# self.net
KiCad netlist of a schematic drawn in Altium Designer
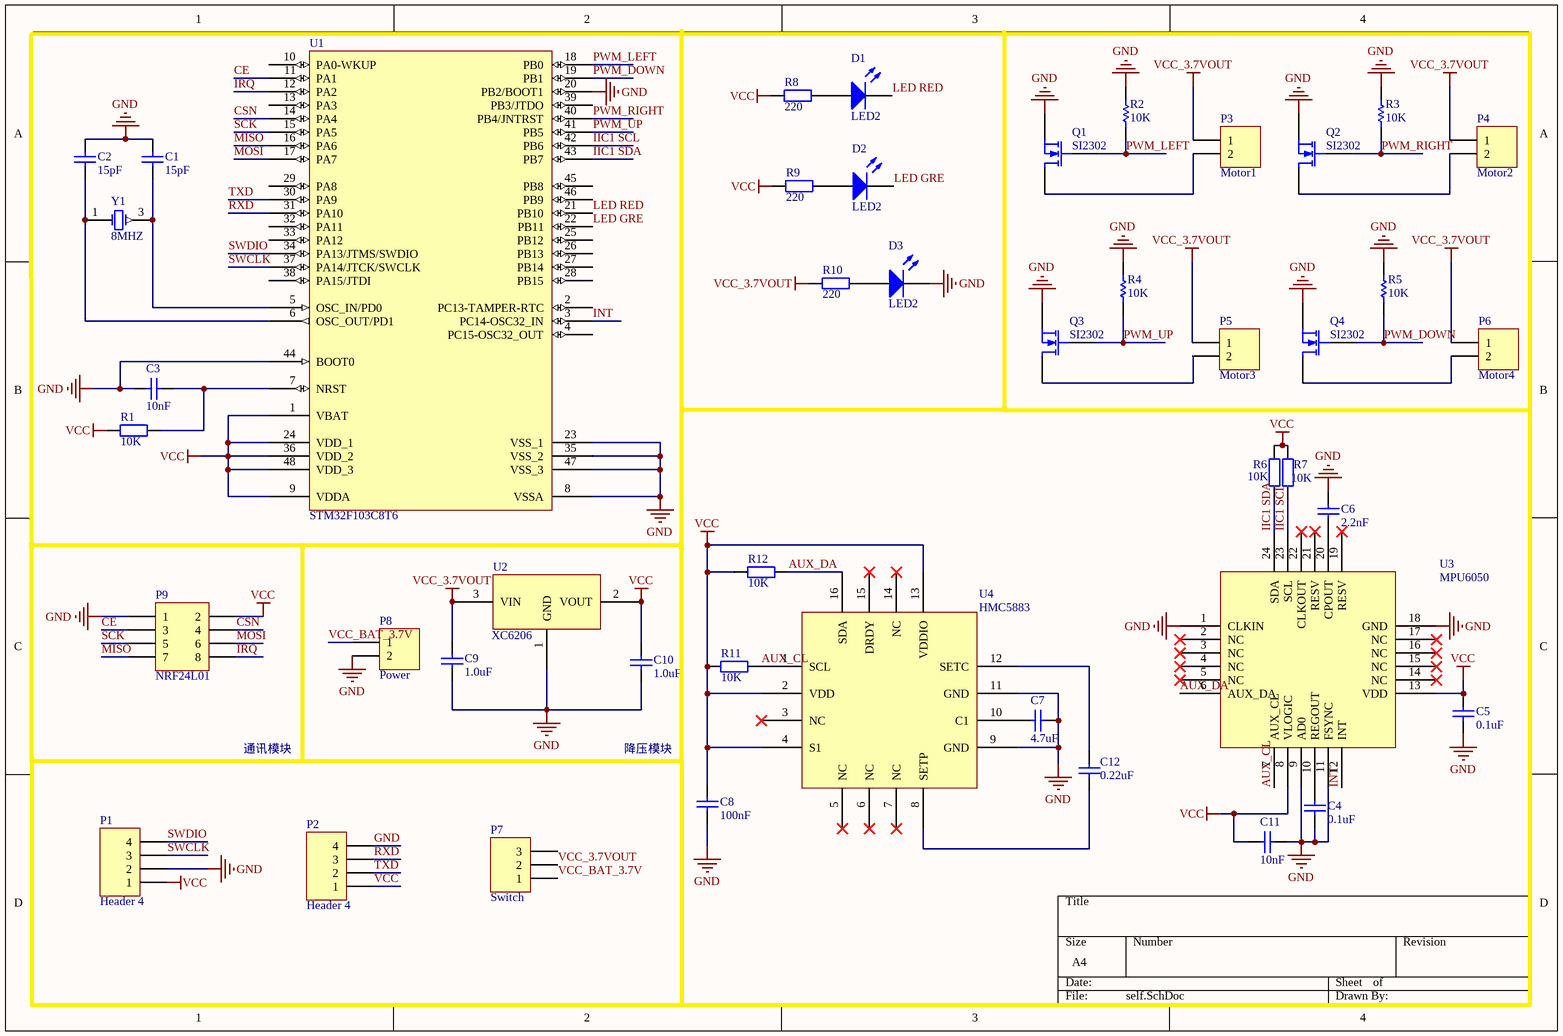
[diagram p0: self.SchDoc]

(export (version "E")
  (design (tool "Eeschema 10.0.6"))
  (components
    (comp (ref "C1")
      (value "15pF")
      (footprint "0603-N-CAP")
      (description "Capacitor (Semiconductor SIM Model)")
      (fields (field (name "Comment") "Cap Semi") (field (name "PUBLISHER") "Altium Limited"))
      (libsource (lib "Miscellaneous Devices") (part "Cap Semi"))
    )
    (comp (ref "C2")
      (value "15pF")
      (footprint "0603-N-CAP")
      (description "Capacitor (Semiconductor SIM Model)")
      (fields (field (name "Comment") "Cap Semi") (field (name "PUBLISHER") "Altium Limited"))
      (libsource (lib "Miscellaneous Devices") (part "Cap Semi"))
    )
    (comp (ref "C3")
      (value "10nF")
      (footprint "0603-N-CAP")
      (description "Capacitor (Semiconductor SIM Model)")
      (fields (field (name "Comment") "Cap Semi") (field (name "PUBLISHER") "Altium Limited"))
      (libsource (lib "Miscellaneous Devices") (part "Cap Semi"))
    )
    (comp (ref "C4")
      (value "0.1uF")
      (footprint "0603-N-CAP")
      (description "Capacitor (Semiconductor SIM Model)")
      (fields (field (name "Comment") "Cap Semi") (field (name "PUBLISHER") "Altium Limited"))
      (libsource (lib "Miscellaneous Devices") (part "Cap Semi"))
    )
    (comp (ref "C5")
      (value "0.1uF")
      (footprint "0603-N-CAP")
      (description "Capacitor (Semiconductor SIM Model)")
      (fields (field (name "Comment") "Cap Semi") (field (name "PUBLISHER") "Altium Limited"))
      (libsource (lib "Miscellaneous Devices") (part "Cap Semi"))
    )
    (comp (ref "C6")
      (value "2.2nF")
      (footprint "0603-N-CAP")
      (description "Capacitor (Semiconductor SIM Model)")
      (fields (field (name "Comment") "Cap Semi") (field (name "PUBLISHER") "Altium Limited"))
      (libsource (lib "Miscellaneous Devices") (part "Cap Semi"))
    )
    (comp (ref "C7")
      (value "4.7uF")
      (footprint "0603-N-CAP")
      (description "Capacitor (Semiconductor SIM Model)")
      (fields (field (name "Comment") "Cap Semi") (field (name "PUBLISHER") "Altium Limited"))
      (libsource (lib "Miscellaneous Devices") (part "Cap Semi"))
    )
    (comp (ref "C8")
      (value "100nF")
      (footprint "0603-N-CAP")
      (description "Capacitor (Semiconductor SIM Model)")
      (fields (field (name "Comment") "Cap Semi") (field (name "PUBLISHER") "Altium Limited"))
      (libsource (lib "Miscellaneous Devices") (part "Cap Semi"))
    )
    (comp (ref "C9")
      (value "1.0uF")
      (footprint "0603-N-CAP")
      (description "Capacitor (Semiconductor SIM Model)")
      (fields (field (name "Comment") "Cap Semi") (field (name "PUBLISHER") "Altium Limited"))
      (libsource (lib "Miscellaneous Devices") (part "Cap Semi"))
    )
    (comp (ref "C10")
      (value "1.0uF")
      (footprint "0603-N-CAP")
      (description "Capacitor (Semiconductor SIM Model)")
      (fields (field (name "Comment") "Cap Semi") (field (name "PUBLISHER") "Altium Limited"))
      (libsource (lib "Miscellaneous Devices") (part "Cap Semi"))
    )
    (comp (ref "C11")
      (value "10nF")
      (footprint "0603-N-CAP")
      (description "Capacitor (Semiconductor SIM Model)")
      (fields (field (name "Comment") "Cap Semi") (field (name "PUBLISHER") "Altium Limited"))
      (libsource (lib "Miscellaneous Devices") (part "Cap Semi"))
    )
    (comp (ref "C12")
      (value "0.22uF")
      (footprint "0603-N-CAP")
      (description "Capacitor (Semiconductor SIM Model)")
      (fields (field (name "Comment") "Cap Semi") (field (name "PUBLISHER") "Altium Limited"))
      (libsource (lib "Miscellaneous Devices") (part "Cap Semi"))
    )
    (comp (ref "D1")
      (value "LED2")
      (footprint "6-0805_N")
      (description "Typical RED, GREEN, YELLOW, AMBER GaAs LED")
      (fields (field (name "PUBLISHER") "Altium Limited"))
      (libsource (lib "Miscellaneous Devices") (part "LED2"))
    )
    (comp (ref "D2")
      (value "LED2")
      (footprint "6-0805_N")
      (description "Typical RED, GREEN, YELLOW, AMBER GaAs LED")
      (fields (field (name "PUBLISHER") "Altium Limited"))
      (libsource (lib "Miscellaneous Devices") (part "LED2"))
    )
    (comp (ref "D3")
      (value "LED2")
      (footprint "6-0805_N")
      (description "Typical RED, GREEN, YELLOW, AMBER GaAs LED")
      (fields (field (name "PUBLISHER") "Altium Limited"))
      (libsource (lib "Miscellaneous Devices") (part "LED2"))
    )
    (comp (ref "P1")
      (value "Header 4")
      (footprint "SW_download")
      (description "Header, 4-Pin")
      (fields (field (name "PUBLISHER") "Altium Limited"))
      (libsource (lib "Miscellaneous Connectors") (part "Header 4"))
    )
    (comp (ref "P2")
      (value "Header 4")
      (footprint "HDR1X4")
      (description "Header, 4-Pin")
      (fields (field (name "PUBLISHER") "Altium Limited"))
      (libsource (lib "Miscellaneous Connectors") (part "Header 4"))
    )
    (comp (ref "P3")
      (value "Motor1")
      (footprint "Motor")
      (description "Header, 2-Pin")
      (fields (field (name "PUBLISHER") "Altium Limited"))
      (libsource (lib "Miscellaneous Connectors") (part "Header 2"))
    )
    (comp (ref "P4")
      (value "Motor2")
      (footprint "Motor")
      (description "Header, 2-Pin")
      (fields (field (name "PUBLISHER") "Altium Limited"))
      (libsource (lib "Miscellaneous Connectors") (part "Header 2"))
    )
    (comp (ref "P5")
      (value "Motor3")
      (footprint "Motor")
      (description "Header, 2-Pin")
      (fields (field (name "PUBLISHER") "Altium Limited"))
      (libsource (lib "Miscellaneous Connectors") (part "Header 2"))
    )
    (comp (ref "P6")
      (value "Motor4")
      (footprint "Motor")
      (description "Header, 2-Pin")
      (fields (field (name "PUBLISHER") "Altium Limited"))
      (libsource (lib "Miscellaneous Connectors") (part "Header 2"))
    )
    (comp (ref "P7")
      (value "Switch")
      (footprint "SWITCH")
      (description "Header, 3-Pin")
      (fields (field (name "PUBLISHER") "Altium Limited"))
      (libsource (lib "Miscellaneous Connectors") (part "Header 3"))
    )
    (comp (ref "P8")
      (value "Power")
      (footprint "0805")
      (description "Header, 2-Pin")
      (fields (field (name "PUBLISHER") "Altium Limited"))
      (libsource (lib "Miscellaneous Connectors") (part "Header 2"))
    )
    (comp (ref "P9")
      (value "NRF24L01")
      (footprint "HDR2X4")
      (description "Header, 4-Pin, Dual row, Right Angle")
      (fields (field (name "PUBLISHER") "Altium Limited"))
      (libsource (lib "Miscellaneous Connectors") (part "Header 4X2H"))
    )
    (comp (ref "Q1")
      (value "SI2302")
      (footprint "SOT-23")
      (description "N-Channel MOSFET")
      (fields (field (name "PUBLISHER") "Altium Limited"))
      (libsource (lib "Miscellaneous Devices") (part "MOSFET-N"))
    )
    (comp (ref "Q2")
      (value "SI2302")
      (footprint "SOT-23")
      (description "N-Channel MOSFET")
      (fields (field (name "PUBLISHER") "Altium Limited"))
      (libsource (lib "Miscellaneous Devices") (part "MOSFET-N"))
    )
    (comp (ref "Q3")
      (value "SI2302")
      (footprint "SOT-23")
      (description "N-Channel MOSFET")
      (fields (field (name "PUBLISHER") "Altium Limited"))
      (libsource (lib "Miscellaneous Devices") (part "MOSFET-N"))
    )
    (comp (ref "Q4")
      (value "SI2302")
      (footprint "SOT-23")
      (description "N-Channel MOSFET")
      (fields (field (name "PUBLISHER") "Altium Limited"))
      (libsource (lib "Miscellaneous Devices") (part "MOSFET-N"))
    )
    (comp (ref "R1")
      (value "10K")
      (footprint "0603-N-res")
      (description "Resistor")
      (fields (field (name "Comment") "Res2") (field (name "PUBLISHER") "Altium Limited"))
      (libsource (lib "") (part "Res2_1"))
    )
    (comp (ref "R2")
      (value "10K")
      (footprint "0603-N-res")
      (description "Resistor")
      (fields (field (name "Comment") "Res1") (field (name "PUBLISHER") "Altium Limited"))
      (libsource (lib "Miscellaneous Devices") (part "Res1"))
    )
    (comp (ref "R3")
      (value "10K")
      (footprint "0603-N-res")
      (description "Resistor")
      (fields (field (name "Comment") "Res1") (field (name "PUBLISHER") "Altium Limited"))
      (libsource (lib "Miscellaneous Devices") (part "Res1"))
    )
    (comp (ref "R4")
      (value "10K")
      (footprint "0603-N-res")
      (description "Resistor")
      (fields (field (name "Comment") "Res1") (field (name "PUBLISHER") "Altium Limited"))
      (libsource (lib "Miscellaneous Devices") (part "Res1"))
    )
    (comp (ref "R5")
      (value "10K")
      (footprint "0603-N-res")
      (description "Resistor")
      (fields (field (name "Comment") "Res1") (field (name "PUBLISHER") "Altium Limited"))
      (libsource (lib "Miscellaneous Devices") (part "Res1"))
    )
    (comp (ref "R6")
      (value "10K")
      (footprint "0603-N-res")
      (description "Resistor")
      (fields (field (name "Comment") "Res2") (field (name "PUBLISHER") "Altium Limited"))
      (libsource (lib "Miscellaneous Devices") (part "Res2"))
    )
    (comp (ref "R7")
      (value "10K")
      (footprint "0603-N-res")
      (description "Resistor")
      (fields (field (name "Comment") "Res2") (field (name "PUBLISHER") "Altium Limited"))
      (libsource (lib "Miscellaneous Devices") (part "Res2"))
    )
    (comp (ref "R8")
      (value "220")
      (footprint "0603-N-res")
      (description "Resistor")
      (fields (field (name "Comment") "Res2") (field (name "PUBLISHER") "Altium Limited"))
      (libsource (lib "") (part "Res2_1"))
    )
    (comp (ref "R9")
      (value "220")
      (footprint "0603-N-res")
      (description "Resistor")
      (fields (field (name "Comment") "Res2") (field (name "PUBLISHER") "Altium Limited"))
      (libsource (lib "") (part "Res2_1"))
    )
    (comp (ref "R10")
      (value "220")
      (footprint "0603-N-res")
      (description "Resistor")
      (fields (field (name "Comment") "Res2") (field (name "PUBLISHER") "Altium Limited"))
      (libsource (lib "") (part "Res2_1"))
    )
    (comp (ref "R11")
      (value "10K")
      (footprint "0603-N-res")
      (description "Resistor")
      (fields (field (name "Comment") "Res2") (field (name "PUBLISHER") "Altium Limited"))
      (libsource (lib "") (part "Res2_1"))
    )
    (comp (ref "R12")
      (value "10K")
      (footprint "0603-N-res")
      (description "Resistor")
      (fields (field (name "Comment") "Res2") (field (name "PUBLISHER") "Altium Limited"))
      (libsource (lib "") (part "Res2_1"))
    )
    (comp (ref "U1")
      (value "STM32F103C8T6")
      (footprint "LQFP48_N")
      (description "STM32 ARM-based 32-bit MCU with 64 Kbytes Flash, 48-pin LQFP, Industrial Temperature")
      (fields (field (name "PUBLISHER") "Altium Limited"))
      (libsource (lib "ST Microcontroller 32-Bit STM32") (part "STM32F103C8T6"))
    )
    (comp (ref "U2") (value "XC6206") (footprint "SOT-23") (libsource (lib "Mine") (part "XC6206")))
    (comp (ref "U3") (value "MPU6050") (libsource (lib "Mine") (part "MPU6050")))
    (comp (ref "U4") (value "HMC5883") (footprint "HMC5883L") (libsource (lib "Mine") (part "HMC5883")))
    (comp (ref "Y1")
      (value "8MHZ")
      (footprint "5032")
      (description "Crystal Oscillator")
      (fields (field (name "PUBLISHER") "Altium Limited"))
      (libsource (lib "Miscellaneous Devices") (part "XTAL"))
    )
  )
  (nets
    (net (code "1") (name "/AUX_CL") (class "Default")
      (node (ref "R11") (pin "1") (pinfunction "1_1") (pintype "passive"))
      (node (ref "U3") (pin "7") (pinfunction "AUX_CL_7") (pintype "passive"))
      (node (ref "U4") (pin "1") (pinfunction "SCL_1") (pintype "passive"))
    )
    (net (code "2") (name "/AUX_DA") (class "Default")
      (node (ref "R12") (pin "1") (pinfunction "1_1") (pintype "passive"))
      (node (ref "U3") (pin "6") (pinfunction "AUX_DA_6") (pintype "passive"))
      (node (ref "U4") (pin "16") (pinfunction "SDA_16") (pintype "passive"))
    )
    (net (code "3") (name "/CE") (class "Default")
      (node (ref "P9") (pin "3") (pinfunction "3_3") (pintype "passive"))
      (node (ref "U1") (pin "11") (pinfunction "PA1_11") (pintype "bidirectional"))
    )
    (net (code "4") (name "/CSN") (class "Default")
      (node (ref "P9") (pin "4") (pinfunction "4_4") (pintype "passive"))
      (node (ref "U1") (pin "14") (pinfunction "PA4_14") (pintype "bidirectional"))
    )
    (net (code "5") (name "/IIC1 SCL") (class "Default")
      (node (ref "R7") (pin "1") (pinfunction "1_1") (pintype "passive"))
      (node (ref "U1") (pin "42") (pinfunction "PB6_42") (pintype "bidirectional"))
      (node (ref "U3") (pin "23") (pinfunction "SCL_23") (pintype "passive"))
    )
    (net (code "6") (name "/IIC1 SDA") (class "Default")
      (node (ref "R6") (pin "1") (pinfunction "1_1") (pintype "passive"))
      (node (ref "U1") (pin "43") (pinfunction "PB7_43") (pintype "bidirectional"))
      (node (ref "U3") (pin "24") (pinfunction "SDA_24") (pintype "passive"))
    )
    (net (code "7") (name "/INT") (class "Default")
      (node (ref "U1") (pin "3") (pinfunction "PC14-OSC32_IN_3") (pintype "bidirectional"))
      (node (ref "U3") (pin "12") (pinfunction "INT_12") (pintype "passive"))
    )
    (net (code "8") (name "/IRQ") (class "Default")
      (node (ref "P9") (pin "8") (pinfunction "8_8") (pintype "passive"))
      (node (ref "U1") (pin "12") (pinfunction "PA2_12") (pintype "bidirectional"))
    )
    (net (code "9") (name "/LED GRE") (class "Default")
      (node (ref "D2") (pin "2") (pinfunction "K_2") (pintype "passive"))
      (node (ref "U1") (pin "22") (pinfunction "PB11_22") (pintype "bidirectional"))
    )
    (net (code "10") (name "/LED RED") (class "Default")
      (node (ref "D1") (pin "2") (pinfunction "K_2") (pintype "passive"))
      (node (ref "U1") (pin "21") (pinfunction "PB10_21") (pintype "bidirectional"))
    )
    (net (code "11") (name "/MISO") (class "Default")
      (node (ref "P9") (pin "7") (pinfunction "7_7") (pintype "passive"))
      (node (ref "U1") (pin "16") (pinfunction "PA6_16") (pintype "bidirectional"))
    )
    (net (code "12") (name "/MOSI") (class "Default")
      (node (ref "P9") (pin "6") (pinfunction "6_6") (pintype "passive"))
      (node (ref "U1") (pin "17") (pinfunction "PA7_17") (pintype "bidirectional"))
    )
    (net (code "13") (name "/PWM_DOWN") (class "Default")
      (node (ref "Q4") (pin "1") (pinfunction "G_1") (pintype "passive"))
      (node (ref "R5") (pin "1") (pinfunction "1_1") (pintype "passive"))
      (node (ref "U1") (pin "19") (pinfunction "PB1_19") (pintype "bidirectional"))
    )
    (net (code "14") (name "/PWM_LEFT") (class "Default")
      (node (ref "Q1") (pin "1") (pinfunction "G_1") (pintype "passive"))
      (node (ref "R2") (pin "1") (pinfunction "1_1") (pintype "passive"))
      (node (ref "U1") (pin "18") (pinfunction "PB0_18") (pintype "bidirectional"))
    )
    (net (code "15") (name "/PWM_RIGHT") (class "Default")
      (node (ref "Q2") (pin "1") (pinfunction "G_1") (pintype "passive"))
      (node (ref "R3") (pin "1") (pinfunction "1_1") (pintype "passive"))
      (node (ref "U1") (pin "40") (pinfunction "PB4/JNTRST_40") (pintype "bidirectional"))
    )
    (net (code "16") (name "/PWM_UP") (class "Default")
      (node (ref "Q3") (pin "1") (pinfunction "G_1") (pintype "passive"))
      (node (ref "R4") (pin "1") (pinfunction "1_1") (pintype "passive"))
      (node (ref "U1") (pin "41") (pinfunction "PB5_41") (pintype "bidirectional"))
    )
    (net (code "17") (name "/RXD") (class "Default")
      (node (ref "P2") (pin "3") (pinfunction "3_3") (pintype "passive"))
      (node (ref "U1") (pin "31") (pinfunction "PA10_31") (pintype "bidirectional"))
    )
    (net (code "18") (name "/SCK") (class "Default")
      (node (ref "P9") (pin "5") (pinfunction "5_5") (pintype "passive"))
      (node (ref "U1") (pin "15") (pinfunction "PA5_15") (pintype "bidirectional"))
    )
    (net (code "19") (name "/SWCLK") (class "Default")
      (node (ref "P1") (pin "3") (pinfunction "3_3") (pintype "passive"))
      (node (ref "U1") (pin "37") (pinfunction "PA14/JTCK/SWCLK_37") (pintype "bidirectional"))
    )
    (net (code "20") (name "/SWDIO") (class "Default")
      (node (ref "P1") (pin "4") (pinfunction "4_4") (pintype "passive"))
      (node (ref "U1") (pin "34") (pinfunction "PA13/JTMS/SWDIO_34") (pintype "bidirectional"))
    )
    (net (code "21") (name "/TXD") (class "Default")
      (node (ref "P2") (pin "2") (pinfunction "2_2") (pintype "passive"))
      (node (ref "U1") (pin "30") (pinfunction "PA9_30") (pintype "bidirectional"))
    )
    (net (code "22") (name "/VCC_BAT_3.7V") (class "Default")
      (node (ref "P7") (pin "1") (pinfunction "1_1") (pintype "passive"))
      (node (ref "P8") (pin "1") (pinfunction "1_1") (pintype "passive"))
    )
    (net (code "23") (name "GND") (class "Default")
      (node (ref "C1") (pin "1") (pinfunction "1_1") (pintype "passive"))
      (node (ref "C10") (pin "1") (pinfunction "1_1") (pintype "passive"))
      (node (ref "C11") (pin "2") (pinfunction "2_2") (pintype "passive"))
      (node (ref "C2") (pin "2") (pinfunction "2_2") (pintype "passive"))
      (node (ref "C3") (pin "1") (pinfunction "1_1") (pintype "passive"))
      (node (ref "C4") (pin "1") (pinfunction "1_1") (pintype "passive"))
      (node (ref "C5") (pin "1") (pinfunction "1_1") (pintype "passive"))
      (node (ref "C6") (pin "2") (pinfunction "2_2") (pintype "passive"))
      (node (ref "C7") (pin "1") (pinfunction "1_1") (pintype "passive"))
      (node (ref "C8") (pin "1") (pinfunction "1_1") (pintype "passive"))
      (node (ref "C9") (pin "1") (pinfunction "1_1") (pintype "passive"))
      (node (ref "D3") (pin "2") (pinfunction "K_2") (pintype "passive"))
      (node (ref "P1") (pin "2") (pinfunction "2_2") (pintype "passive"))
      (node (ref "P2") (pin "4") (pinfunction "4_4") (pintype "passive"))
      (node (ref "P8") (pin "2") (pinfunction "2_2") (pintype "passive"))
      (node (ref "P9") (pin "1") (pinfunction "1_1") (pintype "passive"))
      (node (ref "Q1") (pin "2") (pinfunction "S_2") (pintype "passive"))
      (node (ref "Q2") (pin "2") (pinfunction "S_2") (pintype "passive"))
      (node (ref "Q3") (pin "2") (pinfunction "S_2") (pintype "passive"))
      (node (ref "Q4") (pin "2") (pinfunction "S_2") (pintype "passive"))
      (node (ref "R2") (pin "2") (pinfunction "2_2") (pintype "passive"))
      (node (ref "R3") (pin "2") (pinfunction "2_2") (pintype "passive"))
      (node (ref "R4") (pin "2") (pinfunction "2_2") (pintype "passive"))
      (node (ref "R5") (pin "2") (pinfunction "2_2") (pintype "passive"))
      (node (ref "U1") (pin "20") (pinfunction "PB2/BOOT1_20") (pintype "bidirectional"))
      (node (ref "U1") (pin "23") (pinfunction "VSS_1_23") (pintype "power_in"))
      (node (ref "U1") (pin "35") (pinfunction "VSS_2_35") (pintype "power_in"))
      (node (ref "U1") (pin "44") (pinfunction "BOOT0_44") (pintype "input"))
      (node (ref "U1") (pin "47") (pinfunction "VSS_3_47") (pintype "power_in"))
      (node (ref "U1") (pin "8") (pinfunction "VSSA_8") (pintype "power_in"))
      (node (ref "U2") (pin "1") (pinfunction "GND_1") (pintype "passive"))
      (node (ref "U3") (pin "1") (pinfunction "CLKIN_1") (pintype "passive"))
      (node (ref "U3") (pin "11") (pinfunction "FSYNC_11") (pintype "passive"))
      (node (ref "U3") (pin "18") (pinfunction "GND_18") (pintype "passive"))
      (node (ref "U3") (pin "9") (pinfunction "AD0_9") (pintype "passive"))
      (node (ref "U4") (pin "11") (pinfunction "GND_11") (pintype "passive"))
      (node (ref "U4") (pin "9") (pinfunction "GND_9") (pintype "passive"))
    )
    (net (code "24") (name "Net-(D1-A)") (class "Default")
      (node (ref "D1") (pin "1") (pinfunction "A_1") (pintype "passive"))
      (node (ref "R8") (pin "1") (pinfunction "1_1") (pintype "passive"))
    )
    (net (code "25") (name "Net-(D2-A)") (class "Default")
      (node (ref "D2") (pin "1") (pinfunction "A_1") (pintype "passive"))
      (node (ref "R9") (pin "1") (pinfunction "1_1") (pintype "passive"))
    )
    (net (code "26") (name "Net-(D3-A)") (class "Default")
      (node (ref "D3") (pin "1") (pinfunction "A_1") (pintype "passive"))
      (node (ref "R10") (pin "1") (pinfunction "1_1") (pintype "passive"))
    )
    (net (code "27") (name "Net-(Q1-D)") (class "Default")
      (node (ref "P3") (pin "2") (pinfunction "2_2") (pintype "passive"))
      (node (ref "Q1") (pin "3") (pinfunction "D_3") (pintype "passive"))
    )
    (net (code "28") (name "Net-(Q2-D)") (class "Default")
      (node (ref "P4") (pin "2") (pinfunction "2_2") (pintype "passive"))
      (node (ref "Q2") (pin "3") (pinfunction "D_3") (pintype "passive"))
    )
    (net (code "29") (name "Net-(Q3-D)") (class "Default")
      (node (ref "P5") (pin "2") (pinfunction "2_2") (pintype "passive"))
      (node (ref "Q3") (pin "3") (pinfunction "D_3") (pintype "passive"))
    )
    (net (code "30") (name "Net-(Q4-D)") (class "Default")
      (node (ref "P6") (pin "2") (pinfunction "2_2") (pintype "passive"))
      (node (ref "Q4") (pin "3") (pinfunction "D_3") (pintype "passive"))
    )
    (net (code "31") (name "Net-(U1-NRST)") (class "Default")
      (node (ref "C3") (pin "2") (pinfunction "2_2") (pintype "passive"))
      (node (ref "R1") (pin "1") (pinfunction "1_1") (pintype "passive"))
      (node (ref "U1") (pin "7") (pinfunction "NRST_7") (pintype "bidirectional"))
    )
    (net (code "32") (name "Net-(U1-OSC_IN{slash}PD0)") (class "Default")
      (node (ref "C1") (pin "2") (pinfunction "2_2") (pintype "passive"))
      (node (ref "U1") (pin "5") (pinfunction "OSC_IN/PD0_5") (pintype "input"))
      (node (ref "Y1") (pin "3") (pinfunction "OSC2_3") (pintype "output"))
    )
    (net (code "33") (name "Net-(U1-OSC_OUT{slash}PD1)") (class "Default")
      (node (ref "C2") (pin "1") (pinfunction "1_1") (pintype "passive"))
      (node (ref "U1") (pin "6") (pinfunction "OSC_OUT/PD1_6") (pintype "output"))
      (node (ref "Y1") (pin "1") (pinfunction "OSC1_1") (pintype "passive"))
    )
    (net (code "34") (name "Net-(U3-CPOUT)") (class "Default")
      (node (ref "C6") (pin "1") (pinfunction "1_1") (pintype "passive"))
      (node (ref "U3") (pin "20") (pinfunction "CPOUT_20") (pintype "passive"))
    )
    (net (code "35") (name "Net-(U3-REGOUT)") (class "Default")
      (node (ref "C4") (pin "2") (pinfunction "2_2") (pintype "passive"))
      (node (ref "U3") (pin "10") (pinfunction "REGOUT_10") (pintype "passive"))
    )
    (net (code "36") (name "Net-(U4-C1)") (class "Default")
      (node (ref "C7") (pin "2") (pinfunction "2_2") (pintype "passive"))
      (node (ref "U4") (pin "10") (pinfunction "C1_10") (pintype "passive"))
    )
    (net (code "37") (name "Net-(U4-SETC)") (class "Default")
      (node (ref "C12") (pin "1") (pinfunction "1_1") (pintype "passive"))
      (node (ref "U4") (pin "12") (pinfunction "SETC_12") (pintype "passive"))
    )
    (net (code "38") (name "Net-(U4-SETP)") (class "Default")
      (node (ref "C12") (pin "2") (pinfunction "2_2") (pintype "passive"))
      (node (ref "U4") (pin "8") (pinfunction "SETP_8") (pintype "passive"))
    )
    (net (code "39") (name "VCC") (class "Default")
      (node (ref "C10") (pin "2") (pinfunction "2_2") (pintype "passive"))
      (node (ref "C11") (pin "1") (pinfunction "1_1") (pintype "passive"))
      (node (ref "C5") (pin "2") (pinfunction "2_2") (pintype "passive"))
      (node (ref "C8") (pin "2") (pinfunction "2_2") (pintype "passive"))
      (node (ref "P1") (pin "1") (pinfunction "1_1") (pintype "passive"))
      (node (ref "P2") (pin "1") (pinfunction "1_1") (pintype "passive"))
      (node (ref "P9") (pin "2") (pinfunction "2_2") (pintype "passive"))
      (node (ref "R1") (pin "2") (pinfunction "2_2") (pintype "passive"))
      (node (ref "R11") (pin "2") (pinfunction "2_2") (pintype "passive"))
      (node (ref "R12") (pin "2") (pinfunction "2_2") (pintype "passive"))
      (node (ref "R6") (pin "2") (pinfunction "2_2") (pintype "passive"))
      (node (ref "R7") (pin "2") (pinfunction "2_2") (pintype "passive"))
      (node (ref "R8") (pin "2") (pinfunction "2_2") (pintype "passive"))
      (node (ref "R9") (pin "2") (pinfunction "2_2") (pintype "passive"))
      (node (ref "U1") (pin "1") (pinfunction "VBAT_1") (pintype "power_in"))
      (node (ref "U1") (pin "24") (pinfunction "VDD_1_24") (pintype "power_in"))
      (node (ref "U1") (pin "36") (pinfunction "VDD_2_36") (pintype "power_in"))
      (node (ref "U1") (pin "48") (pinfunction "VDD_3_48") (pintype "power_in"))
      (node (ref "U1") (pin "9") (pinfunction "VDDA_9") (pintype "power_in"))
      (node (ref "U2") (pin "2") (pinfunction "VOUT_2") (pintype "passive"))
      (node (ref "U3") (pin "13") (pinfunction "VDD_13") (pintype "passive"))
      (node (ref "U3") (pin "8") (pinfunction "VLOGIC_8") (pintype "passive"))
      (node (ref "U4") (pin "13") (pinfunction "VDDIO_13") (pintype "passive"))
      (node (ref "U4") (pin "2") (pinfunction "VDD_2") (pintype "passive"))
      (node (ref "U4") (pin "4") (pinfunction "S1_4") (pintype "passive"))
    )
    (net (code "40") (name "VCC_3.7VOUT") (class "Default")
      (node (ref "C9") (pin "2") (pinfunction "2_2") (pintype "passive"))
      (node (ref "P3") (pin "1") (pinfunction "1_1") (pintype "passive"))
      (node (ref "P4") (pin "1") (pinfunction "1_1") (pintype "passive"))
      (node (ref "P5") (pin "1") (pinfunction "1_1") (pintype "passive"))
      (node (ref "P6") (pin "1") (pinfunction "1_1") (pintype "passive"))
      (node (ref "P7") (pin "2") (pinfunction "2_2") (pintype "passive"))
      (node (ref "R10") (pin "2") (pinfunction "2_2") (pintype "passive"))
      (node (ref "U2") (pin "3") (pinfunction "VIN_3") (pintype "passive"))
    )
    (net (code "41") (name "unconnected-(P7-Pad3)") (class "Default")
      (node (ref "P7") (pin "3") (pinfunction "3_3") (pintype "passive"))
    )
    (net (code "42") (name "unconnected-(U1-PA0-WKUP-Pad10)") (class "Default")
      (node (ref "U1") (pin "10") (pinfunction "PA0-WKUP_10") (pintype "bidirectional"))
    )
    (net (code "43") (name "unconnected-(U1-PA3-Pad13)") (class "Default")
      (node (ref "U1") (pin "13") (pinfunction "PA3_13") (pintype "bidirectional"))
    )
    (net (code "44") (name "unconnected-(U1-PA8-Pad29)") (class "Default")
      (node (ref "U1") (pin "29") (pinfunction "PA8_29") (pintype "bidirectional"))
    )
    (net (code "45") (name "unconnected-(U1-PA11-Pad32)") (class "Default")
      (node (ref "U1") (pin "32") (pinfunction "PA11_32") (pintype "bidirectional"))
    )
    (net (code "46") (name "unconnected-(U1-PA12-Pad33)") (class "Default")
      (node (ref "U1") (pin "33") (pinfunction "PA12_33") (pintype "bidirectional"))
    )
    (net (code "47") (name "unconnected-(U1-PA15{slash}JTDI-Pad38)") (class "Default")
      (node (ref "U1") (pin "38") (pinfunction "PA15/JTDI_38") (pintype "bidirectional"))
    )
    (net (code "48") (name "unconnected-(U1-PB3{slash}JTDO-Pad39)") (class "Default")
      (node (ref "U1") (pin "39") (pinfunction "PB3/JTDO_39") (pintype "bidirectional"))
    )
    (net (code "49") (name "unconnected-(U1-PB8-Pad45)") (class "Default")
      (node (ref "U1") (pin "45") (pinfunction "PB8_45") (pintype "bidirectional"))
    )
    (net (code "50") (name "unconnected-(U1-PB9-Pad46)") (class "Default")
      (node (ref "U1") (pin "46") (pinfunction "PB9_46") (pintype "bidirectional"))
    )
    (net (code "51") (name "unconnected-(U1-PB12-Pad25)") (class "Default")
      (node (ref "U1") (pin "25") (pinfunction "PB12_25") (pintype "bidirectional"))
    )
    (net (code "52") (name "unconnected-(U1-PB13-Pad26)") (class "Default")
      (node (ref "U1") (pin "26") (pinfunction "PB13_26") (pintype "bidirectional"))
    )
    (net (code "53") (name "unconnected-(U1-PB14-Pad27)") (class "Default")
      (node (ref "U1") (pin "27") (pinfunction "PB14_27") (pintype "bidirectional"))
    )
    (net (code "54") (name "unconnected-(U1-PB15-Pad28)") (class "Default")
      (node (ref "U1") (pin "28") (pinfunction "PB15_28") (pintype "bidirectional"))
    )
    (net (code "55") (name "unconnected-(U1-PC13-TAMPER-RTC-Pad2)") (class "Default")
      (node (ref "U1") (pin "2") (pinfunction "PC13-TAMPER-RTC_2") (pintype "bidirectional"))
    )
    (net (code "56") (name "unconnected-(U1-PC15-OSC32_OUT-Pad4)") (class "Default")
      (node (ref "U1") (pin "4") (pinfunction "PC15-OSC32_OUT_4") (pintype "bidirectional"))
    )
    (net (code "57") (name "unconnected-(U3-CLKOUT-Pad22)") (class "Default")
      (node (ref "U3") (pin "22") (pinfunction "CLKOUT_22") (pintype "passive+no_connect"))
    )
    (net (code "58") (name "unconnected-(U3-NC-Pad2)") (class "Default")
      (node (ref "U3") (pin "2") (pinfunction "NC_2") (pintype "passive+no_connect"))
    )
    (net (code "59") (name "unconnected-(U3-NC-Pad3)") (class "Default")
      (node (ref "U3") (pin "3") (pinfunction "NC_3") (pintype "passive+no_connect"))
    )
    (net (code "60") (name "unconnected-(U3-NC-Pad4)") (class "Default")
      (node (ref "U3") (pin "4") (pinfunction "NC_4") (pintype "passive+no_connect"))
    )
    (net (code "61") (name "unconnected-(U3-NC-Pad5)") (class "Default")
      (node (ref "U3") (pin "5") (pinfunction "NC_5") (pintype "passive+no_connect"))
    )
    (net (code "62") (name "unconnected-(U3-NC-Pad14)") (class "Default")
      (node (ref "U3") (pin "14") (pinfunction "NC_14") (pintype "passive+no_connect"))
    )
    (net (code "63") (name "unconnected-(U3-NC-Pad15)") (class "Default")
      (node (ref "U3") (pin "15") (pinfunction "NC_15") (pintype "passive+no_connect"))
    )
    (net (code "64") (name "unconnected-(U3-NC-Pad16)") (class "Default")
      (node (ref "U3") (pin "16") (pinfunction "NC_16") (pintype "passive+no_connect"))
    )
    (net (code "65") (name "unconnected-(U3-NC-Pad17)") (class "Default")
      (node (ref "U3") (pin "17") (pinfunction "NC_17") (pintype "passive+no_connect"))
    )
    (net (code "66") (name "unconnected-(U3-RESV-Pad19)") (class "Default")
      (node (ref "U3") (pin "19") (pinfunction "RESV_19") (pintype "passive+no_connect"))
    )
    (net (code "67") (name "unconnected-(U3-RESV-Pad21)") (class "Default")
      (node (ref "U3") (pin "21") (pinfunction "RESV_21") (pintype "passive+no_connect"))
    )
    (net (code "68") (name "unconnected-(U4-DRDY-Pad15)") (class "Default")
      (node (ref "U4") (pin "15") (pinfunction "DRDY_15") (pintype "passive+no_connect"))
    )
    (net (code "69") (name "unconnected-(U4-NC-Pad3)") (class "Default")
      (node (ref "U4") (pin "3") (pinfunction "NC_3") (pintype "passive+no_connect"))
    )
    (net (code "70") (name "unconnected-(U4-NC-Pad5)") (class "Default")
      (node (ref "U4") (pin "5") (pinfunction "NC_5") (pintype "passive+no_connect"))
    )
    (net (code "71") (name "unconnected-(U4-NC-Pad6)") (class "Default")
      (node (ref "U4") (pin "6") (pinfunction "NC_6") (pintype "passive+no_connect"))
    )
    (net (code "72") (name "unconnected-(U4-NC-Pad7)") (class "Default")
      (node (ref "U4") (pin "7") (pinfunction "NC_7") (pintype "passive+no_connect"))
    )
    (net (code "73") (name "unconnected-(U4-NC-Pad14)") (class "Default")
      (node (ref "U4") (pin "14") (pinfunction "NC_14") (pintype "passive+no_connect"))
    )
  )
)
